# Spring_-_Schematic.net
KiCad netlist of a schematic drawn in EasyEDA
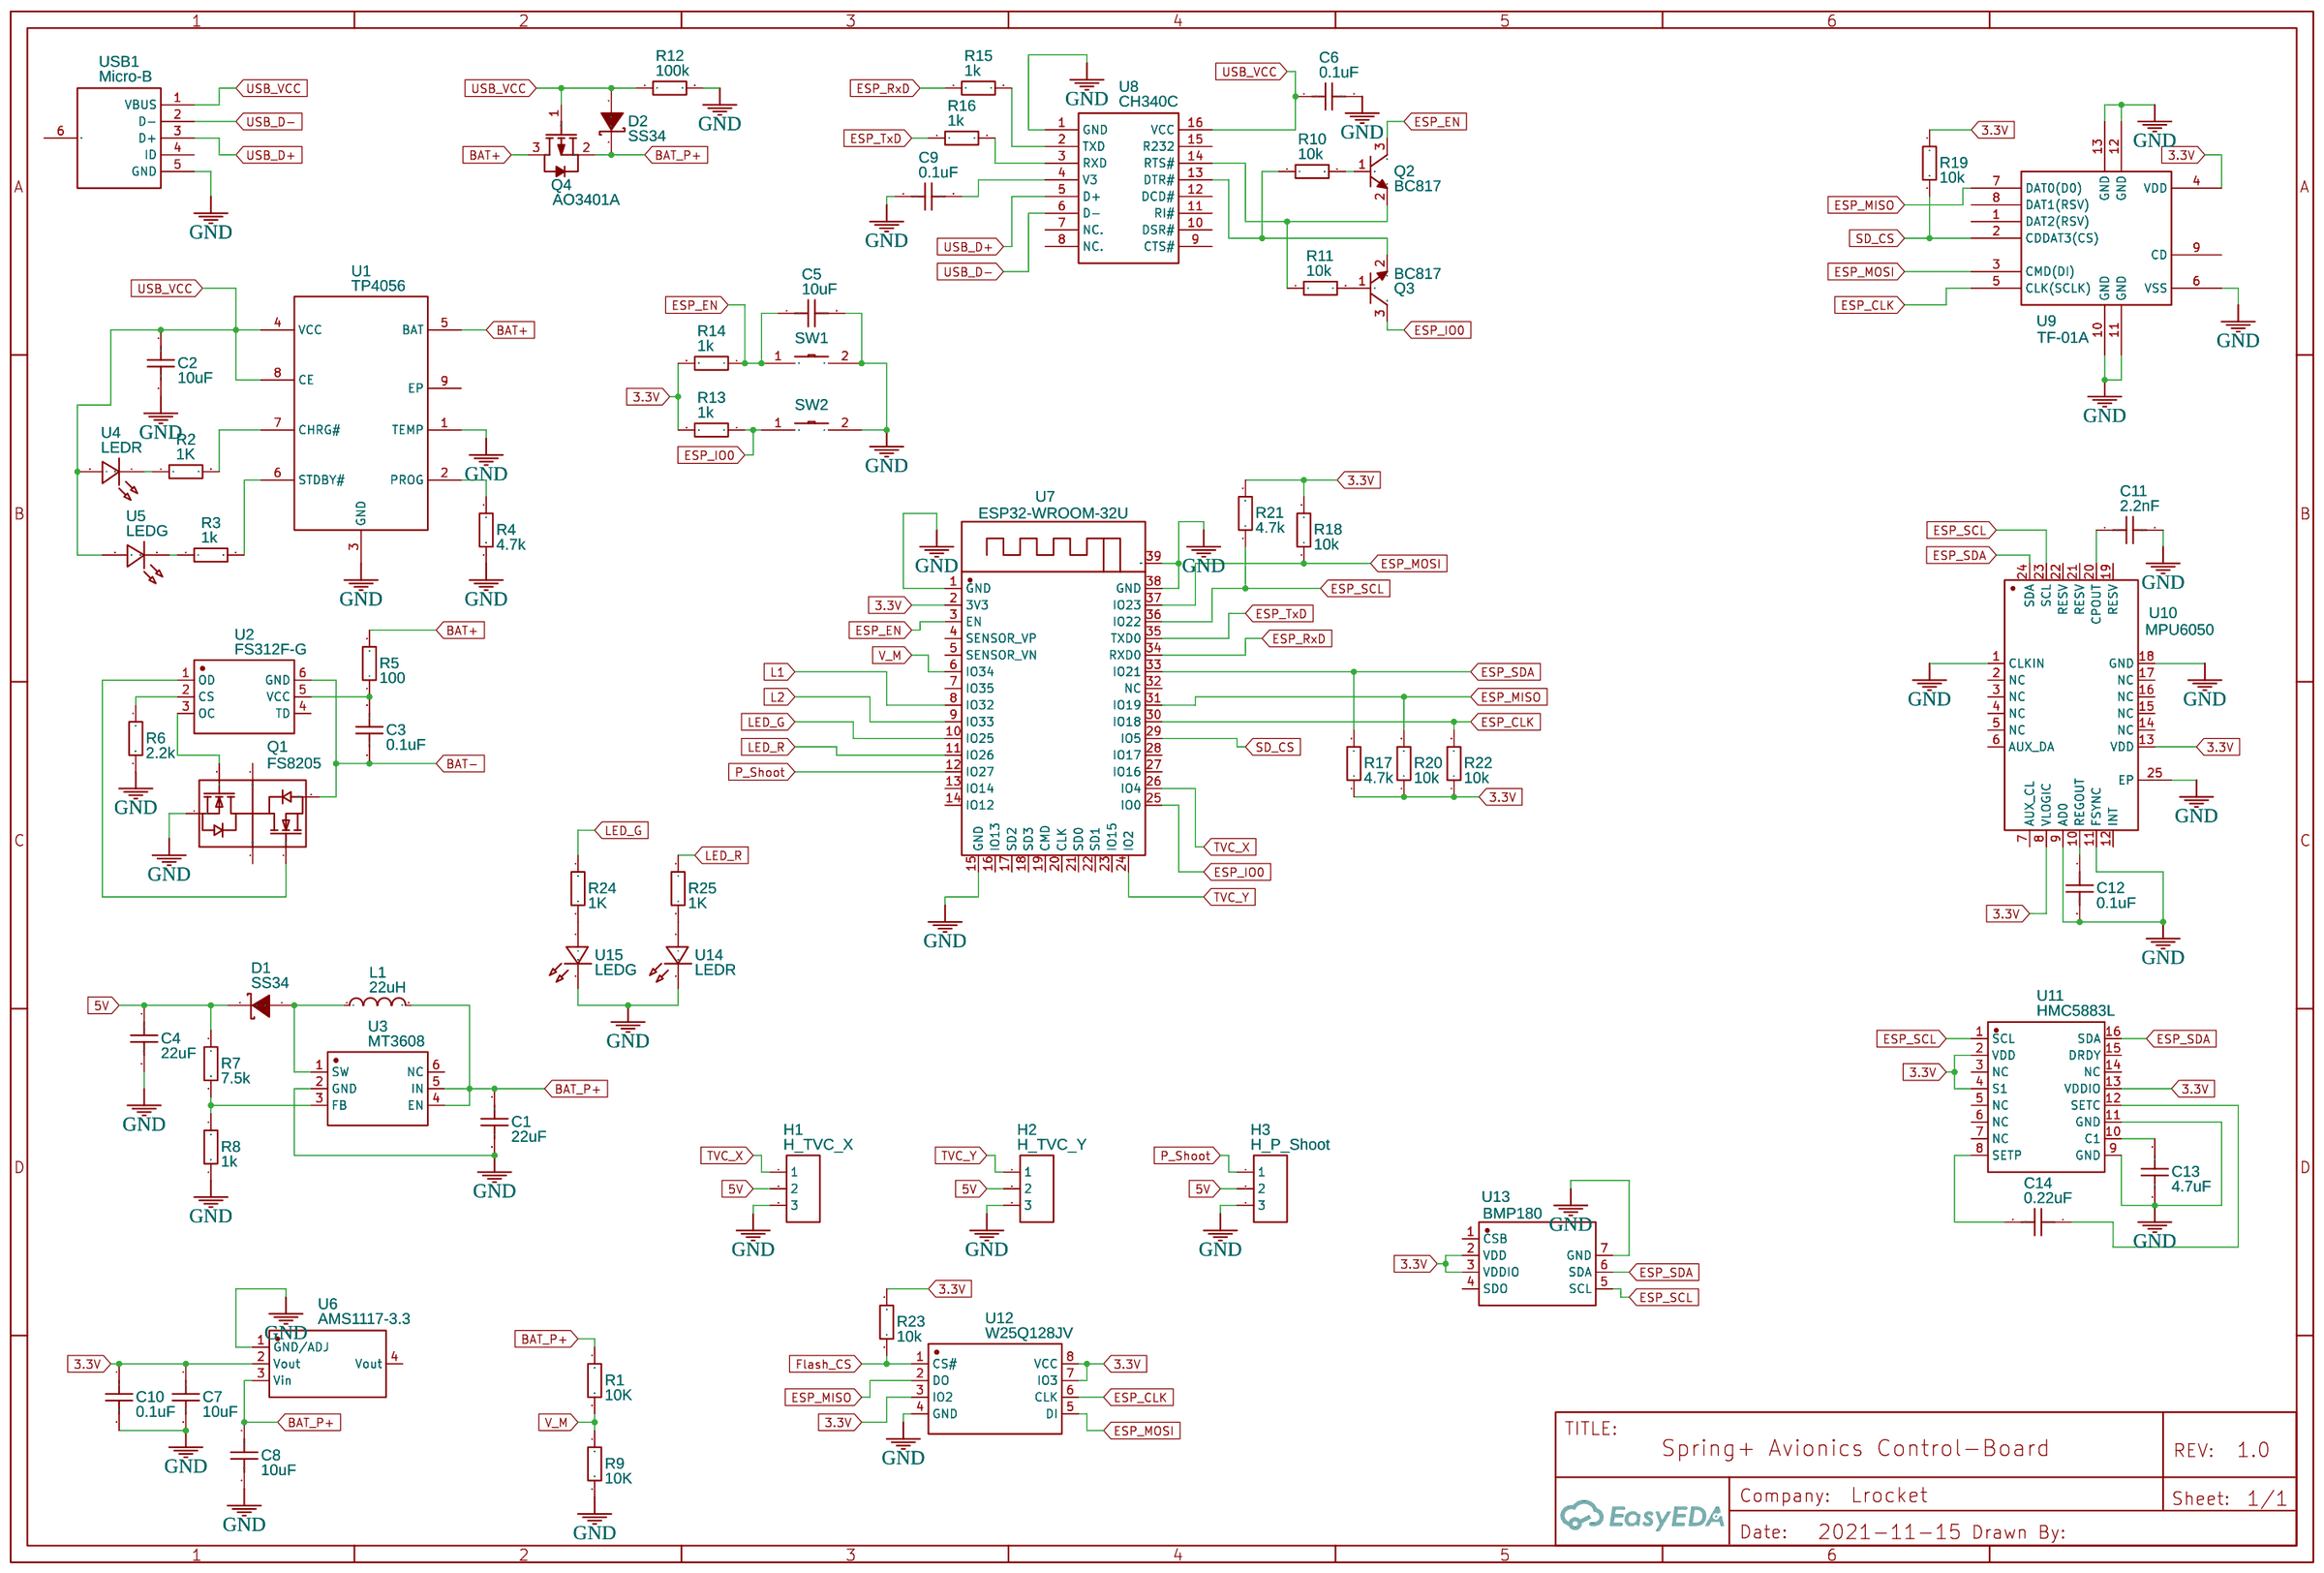
[diagram p0: schematic sheet]

(export (version "E")
  (design (tool "Eeschema 10.0.6"))
  (components
    (comp (ref "C1")
      (value "22uF")
      (fields
        (field (name "BOM_Manufacturer Part") "C1206X5R106K500NT")
        (field (name "BOM_Supplier Part") "C466808")
      )
      (libsource (lib "") (part "C1206X5R106K500NT"))
    )
    (comp (ref "C2")
      (value "10uF")
      (fields
        (field (name "BOM_Manufacturer Part") "C1206X5R106K500NT")
        (field (name "BOM_Supplier Part") "C466808")
      )
      (libsource (lib "") (part "C1206X5R106K500NT"))
    )
    (comp (ref "C3")
      (value "0.1uF")
      (fields
        (field (name "BOM_Manufacturer Part") "C1206X5R106K500NT")
        (field (name "BOM_Supplier Part") "C466808")
      )
      (libsource (lib "") (part "C1206X5R106K500NT_1"))
    )
    (comp (ref "C4")
      (value "22uF")
      (fields
        (field (name "BOM_Manufacturer Part") "C1206X5R106K500NT")
        (field (name "BOM_Supplier Part") "C466808")
      )
      (libsource (lib "") (part "C1206X5R106K500NT"))
    )
    (comp (ref "C5")
      (value "10uF")
      (fields
        (field (name "BOM_Manufacturer Part") "C1206X5R106K500NT")
        (field (name "BOM_Supplier Part") "C466808")
      )
      (libsource (lib "") (part "C1206X5R106K500NT_2"))
    )
    (comp (ref "C6")
      (value "0.1uF")
      (fields
        (field (name "BOM_Manufacturer Part") "C1206X5R106K500NT")
        (field (name "BOM_Supplier Part") "C466808")
      )
      (libsource (lib "") (part "C1206X5R106K500NT_2"))
    )
    (comp (ref "C7")
      (value "10uF")
      (fields
        (field (name "BOM_Manufacturer Part") "C1206X5R106K500NT")
        (field (name "BOM_Supplier Part") "C466808")
      )
      (libsource (lib "") (part "C1206X5R106K500NT"))
    )
    (comp (ref "C8")
      (value "10uF")
      (fields
        (field (name "BOM_Manufacturer Part") "C1206X5R106K500NT")
        (field (name "BOM_Supplier Part") "C466808")
      )
      (libsource (lib "") (part "C1206X5R106K500NT"))
    )
    (comp (ref "C9")
      (value "0.1uF")
      (fields
        (field (name "BOM_Manufacturer Part") "C1206X5R106K500NT")
        (field (name "BOM_Supplier Part") "C466808")
      )
      (libsource (lib "") (part "C1206X5R106K500NT_2"))
    )
    (comp (ref "C10")
      (value "0.1uF")
      (fields
        (field (name "BOM_Manufacturer Part") "C1206X5R106K500NT")
        (field (name "BOM_Supplier Part") "C466808")
      )
      (libsource (lib "") (part "C1206X5R106K500NT"))
    )
    (comp (ref "C11")
      (value "2.2nF")
      (fields
        (field (name "BOM_Manufacturer Part") "C1206X5R106K500NT")
        (field (name "BOM_Supplier Part") "C466808")
      )
      (libsource (lib "") (part "C1206X5R106K500NT_2"))
    )
    (comp (ref "C12")
      (value "0.1uF")
      (fields
        (field (name "BOM_Manufacturer Part") "C1206X5R106K500NT")
        (field (name "BOM_Supplier Part") "C466808")
      )
      (libsource (lib "") (part "C1206X5R106K500NT"))
    )
    (comp (ref "C13")
      (value "4.7uF")
      (fields
        (field (name "BOM_Manufacturer Part") "C1206X5R106K500NT")
        (field (name "BOM_Supplier Part") "C466808")
      )
      (libsource (lib "") (part "C1206X5R106K500NT_1"))
    )
    (comp (ref "C14")
      (value "0.22uF")
      (fields
        (field (name "BOM_Manufacturer Part") "C1206X5R106K500NT")
        (field (name "BOM_Supplier Part") "C466808")
      )
      (libsource (lib "") (part "C1206X5R106K500NT_3"))
    )
    (comp (ref "D1")
      (value "SS34")
      (fields (field (name "BOM_Supplier Part") "C13763"))
      (libsource (lib "") (part "SS34"))
    )
    (comp (ref "D2")
      (value "SS34")
      (fields (field (name "BOM_Supplier Part") "C13763"))
      (libsource (lib "") (part "SS34_1"))
    )
    (comp (ref "H1")
      (value "H_TVC_X")
      (fields
        (field (name "BOM_Manufacturer Part") "Header2.54mm 1*3P")
        (field (name "BOM_Supplier Part") "C49257")
      )
      (libsource (lib "") (part "Header-Male-2.54_1x3"))
    )
    (comp (ref "H2")
      (value "H_TVC_Y")
      (fields
        (field (name "BOM_Manufacturer Part") "Header2.54mm 1*3P")
        (field (name "BOM_Supplier Part") "C49257")
      )
      (libsource (lib "") (part "Header-Male-2.54_1x3"))
    )
    (comp (ref "H3")
      (value "H_P_Shoot")
      (fields
        (field (name "BOM_Manufacturer Part") "Header2.54mm 1*3P")
        (field (name "BOM_Supplier Part") "C49257")
      )
      (libsource (lib "") (part "Header-Male-2.54_1x3"))
    )
    (comp (ref "L1")
      (value "22uH")
      (fields
        (field (name "BOM_Manufacturer Part") "FXL0630-220-M")
        (field (name "BOM_Supplier Part") "C177244")
      )
      (libsource (lib "") (part "FXL0630-220-M"))
    )
    (comp (ref "Q1")
      (value "FS8205")
      (fields (field (name "BOM_Supplier Part") "C32254"))
      (libsource (lib "") (part "FS8205"))
    )
    (comp (ref "Q2")
      (value "BC817")
      (fields (field (name "BOM_Manufacturer Part") "BC817-25") (field (name "BOM_Supplier Part") "C8588"))
      (libsource (lib "") (part "BC817-25_1"))
    )
    (comp (ref "Q3")
      (value "BC817")
      (fields (field (name "BOM_Manufacturer Part") "BC817-25") (field (name "BOM_Supplier Part") "C8588"))
      (libsource (lib "") (part "BC817-25"))
    )
    (comp (ref "Q4")
      (value "AO3401A")
      (fields (field (name "BOM_Supplier Part") "C15127"))
      (libsource (lib "") (part "AO3401A"))
    )
    (comp (ref "R1")
      (value "10K")
      (fields
        (field (name "BOM_Manufacturer Part") "RMCF1206JT10K0")
        (field (name "BOM_Supplier Part") "C237800")
      )
      (libsource (lib "") (part "RMCF1206JT10K0"))
    )
    (comp (ref "R2")
      (value "1K")
      (fields
        (field (name "BOM_Manufacturer Part") "RMCF1206JT10K0")
        (field (name "BOM_Supplier Part") "C237800")
      )
      (libsource (lib "") (part "RMCF1206JT10K0_1"))
    )
    (comp (ref "R3")
      (value "1k")
      (fields
        (field (name "BOM_Manufacturer Part") "RMCF1206JT10K0")
        (field (name "BOM_Supplier Part") "C237800")
      )
      (libsource (lib "") (part "RMCF1206JT10K0_1"))
    )
    (comp (ref "R4")
      (value "4.7k")
      (fields
        (field (name "BOM_Manufacturer Part") "RMCF1206JT10K0")
        (field (name "BOM_Supplier Part") "C237800")
      )
      (libsource (lib "") (part "RMCF1206JT10K0"))
    )
    (comp (ref "R5")
      (value "100")
      (fields
        (field (name "BOM_Manufacturer Part") "RMCF1206JT10K0")
        (field (name "BOM_Supplier Part") "C237800")
      )
      (libsource (lib "") (part "RMCF1206JT10K0_3"))
    )
    (comp (ref "R6")
      (value "2.2k")
      (fields
        (field (name "BOM_Manufacturer Part") "RMCF1206JT10K0")
        (field (name "BOM_Supplier Part") "C237800")
      )
      (libsource (lib "") (part "RMCF1206JT10K0"))
    )
    (comp (ref "R7")
      (value "7.5k")
      (fields
        (field (name "BOM_Manufacturer Part") "RMCF1206JT10K0")
        (field (name "BOM_Supplier Part") "C237800")
      )
      (libsource (lib "") (part "RMCF1206JT10K0"))
    )
    (comp (ref "R8")
      (value "1k")
      (fields
        (field (name "BOM_Manufacturer Part") "RMCF1206JT10K0")
        (field (name "BOM_Supplier Part") "C237800")
      )
      (libsource (lib "") (part "RMCF1206JT10K0"))
    )
    (comp (ref "R9")
      (value "10K")
      (fields
        (field (name "BOM_Manufacturer Part") "RMCF1206JT10K0")
        (field (name "BOM_Supplier Part") "C237800")
      )
      (libsource (lib "") (part "RMCF1206JT10K0"))
    )
    (comp (ref "R10")
      (value "10k")
      (fields
        (field (name "BOM_Manufacturer Part") "RMCF1206JT10K0")
        (field (name "BOM_Supplier Part") "C237800")
      )
      (libsource (lib "") (part "RMCF1206JT10K0_1"))
    )
    (comp (ref "R11")
      (value "10k")
      (fields
        (field (name "BOM_Manufacturer Part") "RMCF1206JT10K0")
        (field (name "BOM_Supplier Part") "C237800")
      )
      (libsource (lib "") (part "RMCF1206JT10K0_1"))
    )
    (comp (ref "R12")
      (value "100k")
      (fields
        (field (name "BOM_Manufacturer Part") "RMCF1206JT10K0")
        (field (name "BOM_Supplier Part") "C237800")
      )
      (libsource (lib "") (part "RMCF1206JT10K0_1"))
    )
    (comp (ref "R13")
      (value "1k")
      (fields
        (field (name "BOM_Manufacturer Part") "RMCF1206JT10K0")
        (field (name "BOM_Supplier Part") "C237800")
      )
      (libsource (lib "") (part "RMCF1206JT10K0_2"))
    )
    (comp (ref "R14")
      (value "1k")
      (fields
        (field (name "BOM_Manufacturer Part") "RMCF1206JT10K0")
        (field (name "BOM_Supplier Part") "C237800")
      )
      (libsource (lib "") (part "RMCF1206JT10K0_2"))
    )
    (comp (ref "R15")
      (value "1k")
      (fields
        (field (name "BOM_Manufacturer Part") "RMCF1206JT10K0")
        (field (name "BOM_Supplier Part") "C237800")
      )
      (libsource (lib "") (part "RMCF1206JT10K0_1"))
    )
    (comp (ref "R16")
      (value "1k")
      (fields
        (field (name "BOM_Manufacturer Part") "RMCF1206JT10K0")
        (field (name "BOM_Supplier Part") "C237800")
      )
      (libsource (lib "") (part "RMCF1206JT10K0_1"))
    )
    (comp (ref "R17")
      (value "4.7k")
      (fields
        (field (name "BOM_Manufacturer Part") "RMCF1206JT10K0")
        (field (name "BOM_Supplier Part") "C237800")
      )
      (libsource (lib "") (part "RMCF1206JT10K0_3"))
    )
    (comp (ref "R18")
      (value "10k")
      (fields
        (field (name "BOM_Manufacturer Part") "RMCF1206JT10K0")
        (field (name "BOM_Supplier Part") "C237800")
      )
      (libsource (lib "") (part "RMCF1206JT10K0_3"))
    )
    (comp (ref "R19")
      (value "10k")
      (fields
        (field (name "BOM_Manufacturer Part") "RMCF1206JT10K0")
        (field (name "BOM_Supplier Part") "C237800")
      )
      (libsource (lib "") (part "RMCF1206JT10K0"))
    )
    (comp (ref "R20")
      (value "10k")
      (fields
        (field (name "BOM_Manufacturer Part") "RMCF1206JT10K0")
        (field (name "BOM_Supplier Part") "C237800")
      )
      (libsource (lib "") (part "RMCF1206JT10K0_3"))
    )
    (comp (ref "R21")
      (value "4.7k")
      (fields
        (field (name "BOM_Manufacturer Part") "RMCF1206JT10K0")
        (field (name "BOM_Supplier Part") "C237800")
      )
      (libsource (lib "") (part "RMCF1206JT10K0_3"))
    )
    (comp (ref "R22")
      (value "10k")
      (fields
        (field (name "BOM_Manufacturer Part") "RMCF1206JT10K0")
        (field (name "BOM_Supplier Part") "C237800")
      )
      (libsource (lib "") (part "RMCF1206JT10K0_3"))
    )
    (comp (ref "R23")
      (value "10k")
      (fields
        (field (name "BOM_Manufacturer Part") "RMCF1206JT10K0")
        (field (name "BOM_Supplier Part") "C237800")
      )
      (libsource (lib "") (part "RMCF1206JT10K0_3"))
    )
    (comp (ref "R24")
      (value "1K")
      (fields
        (field (name "BOM_Manufacturer Part") "RMCF1206JT10K0")
        (field (name "BOM_Supplier Part") "C237800")
      )
      (libsource (lib "") (part "RMCF1206JT10K0"))
    )
    (comp (ref "R25")
      (value "1K")
      (fields
        (field (name "BOM_Manufacturer Part") "RMCF1206JT10K0")
        (field (name "BOM_Supplier Part") "C237800")
      )
      (libsource (lib "") (part "RMCF1206JT10K0"))
    )
    (comp (ref "SW1")
      (value "TS-1101-C-W")
      (fields (field (name "BOM_Supplier Part") "C318938"))
      (libsource (lib "") (part "TS-1101-C-W"))
    )
    (comp (ref "SW2")
      (value "TS-1101-C-W")
      (fields (field (name "BOM_Supplier Part") "C318938"))
      (libsource (lib "") (part "TS-1101-C-W"))
    )
    (comp (ref "U1")
      (value "TP4056")
      (fields (field (name "BOM_Supplier Part") "C16581"))
      (libsource (lib "") (part "TP4056"))
    )
    (comp (ref "U2")
      (value "FS312F-G")
      (fields (field (name "BOM_Supplier Part") "C82736"))
      (libsource (lib "") (part "FS312F-G"))
    )
    (comp (ref "U3")
      (value "MT3608")
      (fields (field (name "BOM_Supplier Part") "C84817"))
      (libsource (lib "") (part "MT3608"))
    )
    (comp (ref "U4")
      (value "LEDR")
      (fields (field (name "BOM_Manufacturer Part") "SFH 2701") (field (name "BOM_Supplier Part") "C66361"))
      (libsource (lib "") (part "SFH 2701_1"))
    )
    (comp (ref "U5")
      (value "LEDG")
      (fields (field (name "BOM_Manufacturer Part") "SFH 2701") (field (name "BOM_Supplier Part") "C66361"))
      (libsource (lib "") (part "SFH 2701_1"))
    )
    (comp (ref "U6")
      (value "AMS1117-3.3")
      (fields (field (name "BOM_Supplier Part") "C6186"))
      (libsource (lib "") (part "AMS1117-3.3"))
    )
    (comp (ref "U7")
      (value "ESP32-WROOM-32U")
      (fields (field (name "BOM_Supplier Part") "C328062"))
      (libsource (lib "") (part "ESP32-WROOM-32U"))
    )
    (comp (ref "U8")
      (value "CH340C")
      (fields (field (name "BOM_Supplier Part") "C84681"))
      (libsource (lib "") (part "CH340C"))
    )
    (comp (ref "U9")
      (value "TF-01A")
      (fields (field (name "BOM_Supplier Part") "C91145"))
      (libsource (lib "") (part "TF-01A"))
    )
    (comp (ref "U10")
      (value "MPU6050")
      (fields
        (field (name "BOM_Manufacturer Part") "MPU6050-YJLTY")
        (field (name "BOM_Supplier Part") "C2912107")
      )
      (libsource (lib "") (part "MPU6050-YJLTY"))
    )
    (comp (ref "U11")
      (value "HMC5883L")
      (fields (field (name "BOM_Supplier Part") "C2859540"))
      (libsource (lib "") (part "HMC5883L"))
    )
    (comp (ref "U12")
      (value "W25Q128JV")
      (fields
        (field (name "BOM_Manufacturer Part") "W25Q128JVSIQTR")
        (field (name "BOM_Supplier Part") "C97521")
      )
      (libsource (lib "") (part "W25Q128JVSIQTR"))
    )
    (comp (ref "U13")
      (value "BMP180")
      (fields (field (name "BOM_Supplier Part") "C438474"))
      (libsource (lib "") (part "BMP180"))
    )
    (comp (ref "U14")
      (value "LEDR")
      (fields (field (name "BOM_Manufacturer Part") "SFH 2701") (field (name "BOM_Supplier Part") "C66361"))
      (libsource (lib "") (part "SFH 2701"))
    )
    (comp (ref "U15")
      (value "LEDG")
      (fields (field (name "BOM_Manufacturer Part") "SFH 2701") (field (name "BOM_Supplier Part") "C66361"))
      (libsource (lib "") (part "SFH 2701"))
    )
    (comp (ref "USB1")
      (value "Micro-B")
      (fields
        (field (name "BOM_Manufacturer Part") "U254-051T-4BH83-S1S")
        (field (name "BOM_Supplier Part") "C319160")
      )
      (libsource (lib "") (part "U254-051T-4BH83-S1S"))
    )
  )
  (nets
    (net (code "1") (name "3.3V") (class "Default")
      (node (ref "C10") (pin "1") (pinfunction "1_1") (pintype "unspecified"))
      (node (ref "C7") (pin "1") (pinfunction "1_1") (pintype "unspecified"))
      (node (ref "R13") (pin "2") (pinfunction "2_2") (pintype "unspecified"))
      (node (ref "R14") (pin "2") (pinfunction "2_2") (pintype "unspecified"))
      (node (ref "R17") (pin "1") (pinfunction "1_1") (pintype "unspecified"))
      (node (ref "R18") (pin "2") (pinfunction "2_2") (pintype "unspecified"))
      (node (ref "R19") (pin "1") (pinfunction "1_1") (pintype "unspecified"))
      (node (ref "R20") (pin "1") (pinfunction "1_1") (pintype "unspecified"))
      (node (ref "R21") (pin "2") (pinfunction "2_2") (pintype "unspecified"))
      (node (ref "R22") (pin "1") (pinfunction "1_1") (pintype "unspecified"))
      (node (ref "R23") (pin "2") (pinfunction "2_2") (pintype "unspecified"))
      (node (ref "U10") (pin "13") (pinfunction "VDD_13") (pintype "unspecified"))
      (node (ref "U10") (pin "8") (pinfunction "VLOGIC_8") (pintype "unspecified"))
      (node (ref "U11") (pin "13") (pinfunction "VDDIO_13") (pintype "unspecified"))
      (node (ref "U11") (pin "2") (pinfunction "VDD_2") (pintype "unspecified"))
      (node (ref "U11") (pin "4") (pinfunction "S1_4") (pintype "unspecified"))
      (node (ref "U12") (pin "3") (pinfunction "IO2_3") (pintype "unspecified"))
      (node (ref "U12") (pin "7") (pinfunction "IO3_7") (pintype "unspecified"))
      (node (ref "U12") (pin "8") (pinfunction "VCC_8") (pintype "unspecified"))
      (node (ref "U13") (pin "2") (pinfunction "VDD_2") (pintype "unspecified"))
      (node (ref "U13") (pin "3") (pinfunction "VDDIO_3") (pintype "unspecified"))
      (node (ref "U6") (pin "2") (pinfunction "Vout_2") (pintype "unspecified"))
      (node (ref "U7") (pin "2") (pinfunction "3V3_2") (pintype "unspecified"))
      (node (ref "U9") (pin "4") (pinfunction "VDD_4") (pintype "input"))
    )
    (net (code "2") (name "5V") (class "Default")
      (node (ref "C4") (pin "1") (pinfunction "1_1") (pintype "unspecified"))
      (node (ref "D1") (pin "2") (pinfunction "K_2") (pintype "unspecified"))
      (node (ref "H1") (pin "2") (pinfunction "2_2") (pintype "input"))
      (node (ref "H2") (pin "2") (pinfunction "2_2") (pintype "input"))
      (node (ref "H3") (pin "2") (pinfunction "2_2") (pintype "input"))
      (node (ref "R7") (pin "1") (pinfunction "1_1") (pintype "unspecified"))
    )
    (net (code "3") (name "BAT+") (class "Default")
      (node (ref "Q4") (pin "3") (pinfunction "D_3") (pintype "unspecified"))
      (node (ref "R5") (pin "2") (pinfunction "2_2") (pintype "unspecified"))
      (node (ref "U1") (pin "5") (pinfunction "BAT_5") (pintype "unspecified"))
    )
    (net (code "4") (name "BAT-") (class "Default")
      (node (ref "C3") (pin "1") (pinfunction "1_1") (pintype "unspecified"))
      (node (ref "Q1") (pin "3") (pinfunction "S2_3") (pintype "unspecified"))
      (node (ref "U2") (pin "6") (pinfunction "GND_6") (pintype "unspecified"))
    )
    (net (code "5") (name "BAT_P+") (class "Default")
      (node (ref "C1") (pin "1") (pinfunction "1_1") (pintype "unspecified"))
      (node (ref "C8") (pin "1") (pinfunction "1_1") (pintype "unspecified"))
      (node (ref "D2") (pin "2") (pinfunction "K_2") (pintype "unspecified"))
      (node (ref "L1") (pin "2") (pinfunction "2_2") (pintype "unspecified"))
      (node (ref "Q4") (pin "2") (pinfunction "S_2") (pintype "unspecified"))
      (node (ref "R1") (pin "1") (pinfunction "1_1") (pintype "unspecified"))
      (node (ref "U3") (pin "4") (pinfunction "EN_4") (pintype "unspecified"))
      (node (ref "U3") (pin "5") (pinfunction "IN_5") (pintype "unspecified"))
      (node (ref "U6") (pin "3") (pinfunction "Vin_3") (pintype "unspecified"))
    )
    (net (code "6") (name "ESP_CLK") (class "Default")
      (node (ref "R22") (pin "2") (pinfunction "2_2") (pintype "unspecified"))
      (node (ref "U12") (pin "6") (pinfunction "CLK_6") (pintype "unspecified"))
      (node (ref "U7") (pin "30") (pinfunction "IO18_30") (pintype "unspecified"))
      (node (ref "U9") (pin "5") (pinfunction "CLK(SCLK)_5") (pintype "input"))
    )
    (net (code "7") (name "ESP_EN") (class "Default")
      (node (ref "C5") (pin "1") (pinfunction "1_1") (pintype "unspecified"))
      (node (ref "Q2") (pin "3") (pinfunction "C_3") (pintype "unspecified"))
      (node (ref "R14") (pin "1") (pinfunction "1_1") (pintype "unspecified"))
      (node (ref "SW1") (pin "1") (pinfunction "1_1") (pintype "unspecified"))
      (node (ref "U7") (pin "3") (pinfunction "EN_3") (pintype "unspecified"))
    )
    (net (code "8") (name "ESP_IO0") (class "Default")
      (node (ref "Q3") (pin "3") (pinfunction "C_3") (pintype "unspecified"))
      (node (ref "R13") (pin "1") (pinfunction "1_1") (pintype "unspecified"))
      (node (ref "SW2") (pin "1") (pinfunction "1_1") (pintype "unspecified"))
      (node (ref "U7") (pin "25") (pinfunction "IO0_25") (pintype "unspecified"))
    )
    (net (code "9") (name "ESP_MISO") (class "Default")
      (node (ref "R20") (pin "2") (pinfunction "2_2") (pintype "unspecified"))
      (node (ref "U12") (pin "2") (pinfunction "DO_2") (pintype "unspecified"))
      (node (ref "U7") (pin "31") (pinfunction "IO19_31") (pintype "unspecified"))
      (node (ref "U9") (pin "7") (pinfunction "DAT0(D0)_7") (pintype "bidirectional"))
    )
    (net (code "10") (name "ESP_MOSI") (class "Default")
      (node (ref "R18") (pin "1") (pinfunction "1_1") (pintype "unspecified"))
      (node (ref "U12") (pin "5") (pinfunction "DI_5") (pintype "unspecified"))
      (node (ref "U7") (pin "37") (pinfunction "IO23_37") (pintype "unspecified"))
      (node (ref "U9") (pin "3") (pinfunction "CMD(DI)_3") (pintype "input"))
    )
    (net (code "11") (name "ESP_RxD") (class "Default")
      (node (ref "R15") (pin "1") (pinfunction "1_1") (pintype "unspecified"))
      (node (ref "U7") (pin "34") (pinfunction "RXD0_34") (pintype "unspecified"))
    )
    (net (code "12") (name "ESP_SCL") (class "Default")
      (node (ref "R21") (pin "1") (pinfunction "1_1") (pintype "unspecified"))
      (node (ref "U10") (pin "23") (pinfunction "SCL_23") (pintype "unspecified"))
      (node (ref "U11") (pin "1") (pinfunction "SCL_1") (pintype "unspecified"))
      (node (ref "U13") (pin "5") (pinfunction "SCL_5") (pintype "unspecified"))
      (node (ref "U7") (pin "36") (pinfunction "IO22_36") (pintype "unspecified"))
    )
    (net (code "13") (name "ESP_SDA") (class "Default")
      (node (ref "R17") (pin "2") (pinfunction "2_2") (pintype "unspecified"))
      (node (ref "U10") (pin "24") (pinfunction "SDA_24") (pintype "unspecified"))
      (node (ref "U11") (pin "16") (pinfunction "SDA_16") (pintype "unspecified"))
      (node (ref "U13") (pin "6") (pinfunction "SDA_6") (pintype "unspecified"))
      (node (ref "U7") (pin "33") (pinfunction "IO21_33") (pintype "unspecified"))
    )
    (net (code "14") (name "ESP_TxD") (class "Default")
      (node (ref "R16") (pin "1") (pinfunction "1_1") (pintype "unspecified"))
      (node (ref "U7") (pin "35") (pinfunction "TXD0_35") (pintype "unspecified"))
    )
    (net (code "15") (name "Flash_CS") (class "Default")
      (node (ref "R23") (pin "1") (pinfunction "1_1") (pintype "unspecified"))
      (node (ref "U12") (pin "1") (pinfunction "CS#_1") (pintype "unspecified"))
    )
    (net (code "16") (name "GND") (class "Default")
      (node (ref "C1") (pin "2") (pinfunction "2_2") (pintype "unspecified"))
      (node (ref "C10") (pin "2") (pinfunction "2_2") (pintype "unspecified"))
      (node (ref "C11") (pin "2") (pinfunction "2_2") (pintype "unspecified"))
      (node (ref "C12") (pin "2") (pinfunction "2_2") (pintype "unspecified"))
      (node (ref "C13") (pin "1") (pinfunction "1_1") (pintype "unspecified"))
      (node (ref "C2") (pin "2") (pinfunction "2_2") (pintype "unspecified"))
      (node (ref "C4") (pin "2") (pinfunction "2_2") (pintype "unspecified"))
      (node (ref "C5") (pin "2") (pinfunction "2_2") (pintype "unspecified"))
      (node (ref "C6") (pin "2") (pinfunction "2_2") (pintype "unspecified"))
      (node (ref "C7") (pin "2") (pinfunction "2_2") (pintype "unspecified"))
      (node (ref "C8") (pin "2") (pinfunction "2_2") (pintype "unspecified"))
      (node (ref "C9") (pin "1") (pinfunction "1_1") (pintype "unspecified"))
      (node (ref "H1") (pin "3") (pinfunction "3_3") (pintype "input"))
      (node (ref "H2") (pin "3") (pinfunction "3_3") (pintype "input"))
      (node (ref "H3") (pin "3") (pinfunction "3_3") (pintype "input"))
      (node (ref "Q1") (pin "1") (pinfunction "S1_1") (pintype "unspecified"))
      (node (ref "R12") (pin "2") (pinfunction "2_2") (pintype "unspecified"))
      (node (ref "R4") (pin "2") (pinfunction "2_2") (pintype "unspecified"))
      (node (ref "R6") (pin "2") (pinfunction "2_2") (pintype "unspecified"))
      (node (ref "R8") (pin "2") (pinfunction "2_2") (pintype "unspecified"))
      (node (ref "R9") (pin "2") (pinfunction "2_2") (pintype "unspecified"))
      (node (ref "SW1") (pin "2") (pinfunction "2_2") (pintype "unspecified"))
      (node (ref "SW2") (pin "2") (pinfunction "2_2") (pintype "unspecified"))
      (node (ref "U1") (pin "1") (pinfunction "TEMP_1") (pintype "unspecified"))
      (node (ref "U1") (pin "3") (pinfunction "GND_3") (pintype "unspecified"))
      (node (ref "U10") (pin "1") (pinfunction "CLKIN_1") (pintype "unspecified"))
      (node (ref "U10") (pin "11") (pinfunction "FSYNC_11") (pintype "unspecified"))
      (node (ref "U10") (pin "18") (pinfunction "GND_18") (pintype "unspecified"))
      (node (ref "U10") (pin "25") (pinfunction "EP_25") (pintype "unspecified"))
      (node (ref "U10") (pin "9") (pinfunction "AD0_9") (pintype "unspecified"))
      (node (ref "U11") (pin "11") (pinfunction "GND_11") (pintype "unspecified"))
      (node (ref "U11") (pin "9") (pinfunction "GND_9") (pintype "unspecified"))
      (node (ref "U12") (pin "4") (pinfunction "GND_4") (pintype "unspecified"))
      (node (ref "U13") (pin "7") (pinfunction "GND_7") (pintype "unspecified"))
      (node (ref "U14") (pin "1") (pinfunction "C_1") (pintype "unspecified"))
      (node (ref "U15") (pin "1") (pinfunction "C_1") (pintype "unspecified"))
      (node (ref "U3") (pin "2") (pinfunction "GND_2") (pintype "unspecified"))
      (node (ref "U6") (pin "1") (pinfunction "GND/ADJ_1") (pintype "unspecified"))
      (node (ref "U7") (pin "1") (pinfunction "GND_1") (pintype "unspecified"))
      (node (ref "U7") (pin "15") (pinfunction "GND_15") (pintype "unspecified"))
      (node (ref "U7") (pin "38") (pinfunction "GND_38") (pintype "unspecified"))
      (node (ref "U7") (pin "39") (pinfunction "GND_39") (pintype "unspecified"))
      (node (ref "U8") (pin "1") (pinfunction "GND_1") (pintype "unspecified"))
      (node (ref "U9") (pin "10") (pinfunction "GND_10") (pintype "input"))
      (node (ref "U9") (pin "11") (pinfunction "GND_11") (pintype "input"))
      (node (ref "U9") (pin "12") (pinfunction "GND_12") (pintype "input"))
      (node (ref "U9") (pin "13") (pinfunction "GND_13") (pintype "input"))
      (node (ref "U9") (pin "6") (pinfunction "VSS_6") (pintype "input"))
      (node (ref "USB1") (pin "5") (pinfunction "GND_5") (pintype "input"))
    )
    (net (code "17") (name "L1") (class "Default")
      (node (ref "U7") (pin "8") (pinfunction "IO32_8") (pintype "unspecified"))
    )
    (net (code "18") (name "L2") (class "Default")
      (node (ref "U7") (pin "9") (pinfunction "IO33_9") (pintype "unspecified"))
    )
    (net (code "19") (name "LED_G") (class "Default")
      (node (ref "R24") (pin "1") (pinfunction "1_1") (pintype "unspecified"))
      (node (ref "U7") (pin "10") (pinfunction "IO25_10") (pintype "unspecified"))
    )
    (net (code "20") (name "LED_R") (class "Default")
      (node (ref "R25") (pin "1") (pinfunction "1_1") (pintype "unspecified"))
      (node (ref "U7") (pin "11") (pinfunction "IO26_11") (pintype "unspecified"))
    )
    (net (code "21") (name "Net-(D1-A)") (class "Default")
      (node (ref "D1") (pin "1") (pinfunction "A_1") (pintype "unspecified"))
      (node (ref "L1") (pin "1") (pinfunction "1_1") (pintype "unspecified"))
      (node (ref "U3") (pin "1") (pinfunction "SW_1") (pintype "unspecified"))
    )
    (net (code "22") (name "Net-(Q1-G1)") (class "Default")
      (node (ref "Q1") (pin "6") (pinfunction "G1_6") (pintype "unspecified"))
      (node (ref "U2") (pin "3") (pinfunction "OC_3") (pintype "unspecified"))
    )
    (net (code "23") (name "Net-(Q1-G2)") (class "Default")
      (node (ref "Q1") (pin "4") (pinfunction "G2_4") (pintype "unspecified"))
      (node (ref "U2") (pin "1") (pinfunction "OD_1") (pintype "unspecified"))
    )
    (net (code "24") (name "Net-(Q2-B)") (class "Default")
      (node (ref "Q2") (pin "1") (pinfunction "B_1") (pintype "unspecified"))
      (node (ref "R10") (pin "2") (pinfunction "2_2") (pintype "unspecified"))
    )
    (net (code "25") (name "Net-(Q2-E)") (class "Default")
      (node (ref "Q2") (pin "2") (pinfunction "E_2") (pintype "unspecified"))
      (node (ref "R11") (pin "1") (pinfunction "1_1") (pintype "unspecified"))
      (node (ref "U8") (pin "14") (pinfunction "RTS#_14") (pintype "unspecified"))
    )
    (net (code "26") (name "Net-(Q3-B)") (class "Default")
      (node (ref "Q3") (pin "1") (pinfunction "B_1") (pintype "unspecified"))
      (node (ref "R11") (pin "2") (pinfunction "2_2") (pintype "unspecified"))
    )
    (net (code "27") (name "Net-(Q3-E)") (class "Default")
      (node (ref "Q3") (pin "2") (pinfunction "E_2") (pintype "unspecified"))
      (node (ref "R10") (pin "1") (pinfunction "1_1") (pintype "unspecified"))
      (node (ref "U8") (pin "13") (pinfunction "DTR#_13") (pintype "unspecified"))
    )
    (net (code "28") (name "Net-(U1-CHRG#)") (class "Default")
      (node (ref "R2") (pin "2") (pinfunction "2_2") (pintype "unspecified"))
      (node (ref "U1") (pin "7") (pinfunction "CHRG#_7") (pintype "unspecified"))
    )
    (net (code "29") (name "Net-(U1-PROG)") (class "Default")
      (node (ref "R4") (pin "1") (pinfunction "1_1") (pintype "unspecified"))
      (node (ref "U1") (pin "2") (pinfunction "PROG_2") (pintype "unspecified"))
    )
    (net (code "30") (name "Net-(U1-STDBY#)") (class "Default")
      (node (ref "R3") (pin "2") (pinfunction "2_2") (pintype "unspecified"))
      (node (ref "U1") (pin "6") (pinfunction "STDBY#_6") (pintype "unspecified"))
    )
    (net (code "31") (name "Net-(U2-CS)") (class "Default")
      (node (ref "R6") (pin "1") (pinfunction "1_1") (pintype "unspecified"))
      (node (ref "U2") (pin "2") (pinfunction "CS_2") (pintype "unspecified"))
    )
    (net (code "32") (name "Net-(U2-VCC)") (class "Default")
      (node (ref "C3") (pin "2") (pinfunction "2_2") (pintype "unspecified"))
      (node (ref "R5") (pin "1") (pinfunction "1_1") (pintype "unspecified"))
      (node (ref "U2") (pin "5") (pinfunction "VCC_5") (pintype "unspecified"))
    )
    (net (code "33") (name "Net-(U3-FB)") (class "Default")
      (node (ref "R7") (pin "2") (pinfunction "2_2") (pintype "unspecified"))
      (node (ref "R8") (pin "1") (pinfunction "1_1") (pintype "unspecified"))
      (node (ref "U3") (pin "3") (pinfunction "FB_3") (pintype "unspecified"))
    )
    (net (code "34") (name "Net-(U4-C)") (class "Default")
      (node (ref "R2") (pin "1") (pinfunction "1_1") (pintype "unspecified"))
      (node (ref "U4") (pin "1") (pinfunction "C_1") (pintype "unspecified"))
    )
    (net (code "35") (name "Net-(U5-C)") (class "Default")
      (node (ref "R3") (pin "1") (pinfunction "1_1") (pintype "unspecified"))
      (node (ref "U5") (pin "1") (pinfunction "C_1") (pintype "unspecified"))
    )
    (net (code "36") (name "Net-(U8-RXD)") (class "Default")
      (node (ref "R16") (pin "2") (pinfunction "2_2") (pintype "unspecified"))
      (node (ref "U8") (pin "3") (pinfunction "RXD_3") (pintype "unspecified"))
    )
    (net (code "37") (name "Net-(U8-TXD)") (class "Default")
      (node (ref "R15") (pin "2") (pinfunction "2_2") (pintype "unspecified"))
      (node (ref "U8") (pin "2") (pinfunction "TXD_2") (pintype "unspecified"))
    )
    (net (code "38") (name "Net-(U8-V3)") (class "Default")
      (node (ref "C9") (pin "2") (pinfunction "2_2") (pintype "unspecified"))
      (node (ref "U8") (pin "4") (pinfunction "V3_4") (pintype "unspecified"))
    )
    (net (code "39") (name "Net-(U10-CPOUT)") (class "Default")
      (node (ref "C11") (pin "1") (pinfunction "1_1") (pintype "unspecified"))
      (node (ref "U10") (pin "20") (pinfunction "CPOUT_20") (pintype "unspecified"))
    )
    (net (code "40") (name "Net-(U10-REGOUT)") (class "Default")
      (node (ref "C12") (pin "1") (pinfunction "1_1") (pintype "unspecified"))
      (node (ref "U10") (pin "10") (pinfunction "REGOUT_10") (pintype "unspecified"))
    )
    (net (code "41") (name "Net-(U11-C1)") (class "Default")
      (node (ref "C13") (pin "2") (pinfunction "2_2") (pintype "unspecified"))
      (node (ref "U11") (pin "10") (pinfunction "C1_10") (pintype "unspecified"))
    )
    (net (code "42") (name "Net-(U11-SETC)") (class "Default")
      (node (ref "C14") (pin "1") (pinfunction "1_1") (pintype "unspecified"))
      (node (ref "U11") (pin "12") (pinfunction "SETC_12") (pintype "unspecified"))
    )
    (net (code "43") (name "Net-(U11-SETP)") (class "Default")
      (node (ref "C14") (pin "2") (pinfunction "2_2") (pintype "unspecified"))
      (node (ref "U11") (pin "8") (pinfunction "SETP_8") (pintype "unspecified"))
    )
    (net (code "44") (name "Net-(U14-A)") (class "Default")
      (node (ref "R25") (pin "2") (pinfunction "2_2") (pintype "unspecified"))
      (node (ref "U14") (pin "2") (pinfunction "A_2") (pintype "unspecified"))
    )
    (net (code "45") (name "Net-(U15-A)") (class "Default")
      (node (ref "R24") (pin "2") (pinfunction "2_2") (pintype "unspecified"))
      (node (ref "U15") (pin "2") (pinfunction "A_2") (pintype "unspecified"))
    )
    (net (code "46") (name "P_Shoot") (class "Default")
      (node (ref "H3") (pin "1") (pinfunction "1_1") (pintype "input"))
      (node (ref "U7") (pin "12") (pinfunction "IO27_12") (pintype "unspecified"))
    )
    (net (code "47") (name "SD_CS") (class "Default")
      (node (ref "R19") (pin "2") (pinfunction "2_2") (pintype "unspecified"))
      (node (ref "U7") (pin "29") (pinfunction "IO5_29") (pintype "unspecified"))
      (node (ref "U9") (pin "2") (pinfunction "CDDAT3(CS)_2") (pintype "bidirectional"))
    )
    (net (code "48") (name "TVC_X") (class "Default")
      (node (ref "H1") (pin "1") (pinfunction "1_1") (pintype "input"))
      (node (ref "U7") (pin "26") (pinfunction "IO4_26") (pintype "unspecified"))
    )
    (net (code "49") (name "TVC_Y") (class "Default")
      (node (ref "H2") (pin "1") (pinfunction "1_1") (pintype "input"))
      (node (ref "U7") (pin "24") (pinfunction "IO2_24") (pintype "unspecified"))
    )
    (net (code "50") (name "USB_D+") (class "Default")
      (node (ref "U8") (pin "5") (pinfunction "D+_5") (pintype "unspecified"))
      (node (ref "USB1") (pin "3") (pinfunction "D+_3") (pintype "input"))
    )
    (net (code "51") (name "USB_D-") (class "Default")
      (node (ref "U8") (pin "6") (pinfunction "D-_6") (pintype "unspecified"))
      (node (ref "USB1") (pin "2") (pinfunction "D-_2") (pintype "input"))
    )
    (net (code "52") (name "USB_VCC") (class "Default")
      (node (ref "C2") (pin "1") (pinfunction "1_1") (pintype "unspecified"))
      (node (ref "C6") (pin "1") (pinfunction "1_1") (pintype "unspecified"))
      (node (ref "D2") (pin "1") (pinfunction "A_1") (pintype "unspecified"))
      (node (ref "Q4") (pin "1") (pinfunction "G_1") (pintype "unspecified"))
      (node (ref "R12") (pin "1") (pinfunction "1_1") (pintype "unspecified"))
      (node (ref "U1") (pin "4") (pinfunction "VCC_4") (pintype "unspecified"))
      (node (ref "U1") (pin "8") (pinfunction "CE_8") (pintype "unspecified"))
      (node (ref "U4") (pin "2") (pinfunction "A_2") (pintype "unspecified"))
      (node (ref "U5") (pin "2") (pinfunction "A_2") (pintype "unspecified"))
      (node (ref "U8") (pin "16") (pinfunction "VCC_16") (pintype "unspecified"))
      (node (ref "USB1") (pin "1") (pinfunction "VBUS_1") (pintype "input"))
    )
    (net (code "53") (name "V_M") (class "Default")
      (node (ref "R1") (pin "2") (pinfunction "2_2") (pintype "unspecified"))
      (node (ref "R9") (pin "1") (pinfunction "1_1") (pintype "unspecified"))
      (node (ref "U7") (pin "6") (pinfunction "IO34_6") (pintype "unspecified"))
    )
    (net (code "54") (name "unconnected-(Q1-D12-Pad2)") (class "Default")
      (node (ref "Q1") (pin "2") (pinfunction "D12_2") (pintype "unspecified"))
    )
    (net (code "55") (name "unconnected-(Q1-D12-Pad5)") (class "Default")
      (node (ref "Q1") (pin "5") (pinfunction "D12_5") (pintype "unspecified"))
    )
    (net (code "56") (name "unconnected-(U1-EP-Pad9)") (class "Default")
      (node (ref "U1") (pin "9") (pinfunction "EP_9") (pintype "unspecified"))
    )
    (net (code "57") (name "unconnected-(U2-TD-Pad4)") (class "Default")
      (node (ref "U2") (pin "4") (pinfunction "TD_4") (pintype "unspecified"))
    )
    (net (code "58") (name "unconnected-(U3-NC-Pad6)") (class "Default")
      (node (ref "U3") (pin "6") (pinfunction "NC_6") (pintype "unspecified"))
    )
    (net (code "59") (name "unconnected-(U6-Vout-Pad4)") (class "Default")
      (node (ref "U6") (pin "4") (pinfunction "Vout_4") (pintype "unspecified"))
    )
    (net (code "60") (name "unconnected-(U7-CLK-Pad20)") (class "Default")
      (node (ref "U7") (pin "20") (pinfunction "CLK_20") (pintype "unspecified"))
    )
    (net (code "61") (name "unconnected-(U7-CMD-Pad19)") (class "Default")
      (node (ref "U7") (pin "19") (pinfunction "CMD_19") (pintype "unspecified"))
    )
    (net (code "62") (name "unconnected-(U7-IO12-Pad14)") (class "Default")
      (node (ref "U7") (pin "14") (pinfunction "IO12_14") (pintype "unspecified"))
    )
    (net (code "63") (name "unconnected-(U7-IO13-Pad16)") (class "Default")
      (node (ref "U7") (pin "16") (pinfunction "IO13_16") (pintype "unspecified"))
    )
    (net (code "64") (name "unconnected-(U7-IO14-Pad13)") (class "Default")
      (node (ref "U7") (pin "13") (pinfunction "IO14_13") (pintype "unspecified"))
    )
    (net (code "65") (name "unconnected-(U7-IO15-Pad23)") (class "Default")
      (node (ref "U7") (pin "23") (pinfunction "IO15_23") (pintype "unspecified"))
    )
    (net (code "66") (name "unconnected-(U7-IO16-Pad27)") (class "Default")
      (node (ref "U7") (pin "27") (pinfunction "IO16_27") (pintype "unspecified"))
    )
    (net (code "67") (name "unconnected-(U7-IO17-Pad28)") (class "Default")
      (node (ref "U7") (pin "28") (pinfunction "IO17_28") (pintype "unspecified"))
    )
    (net (code "68") (name "unconnected-(U7-IO35-Pad7)") (class "Default")
      (node (ref "U7") (pin "7") (pinfunction "IO35_7") (pintype "unspecified"))
    )
    (net (code "69") (name "unconnected-(U7-NC-Pad32)") (class "Default")
      (node (ref "U7") (pin "32") (pinfunction "NC_32") (pintype "unspecified"))
    )
    (net (code "70") (name "unconnected-(U7-SD0-Pad21)") (class "Default")
      (node (ref "U7") (pin "21") (pinfunction "SD0_21") (pintype "unspecified"))
    )
    (net (code "71") (name "unconnected-(U7-SD1-Pad22)") (class "Default")
      (node (ref "U7") (pin "22") (pinfunction "SD1_22") (pintype "unspecified"))
    )
    (net (code "72") (name "unconnected-(U7-SD2-Pad17)") (class "Default")
      (node (ref "U7") (pin "17") (pinfunction "SD2_17") (pintype "unspecified"))
    )
    (net (code "73") (name "unconnected-(U7-SD3-Pad18)") (class "Default")
      (node (ref "U7") (pin "18") (pinfunction "SD3_18") (pintype "unspecified"))
    )
    (net (code "74") (name "unconnected-(U7-SENSOR_VN-Pad5)") (class "Default")
      (node (ref "U7") (pin "5") (pinfunction "SENSOR_VN_5") (pintype "unspecified"))
    )
    (net (code "75") (name "unconnected-(U7-SENSOR_VP-Pad4)") (class "Default")
      (node (ref "U7") (pin "4") (pinfunction "SENSOR_VP_4") (pintype "unspecified"))
    )
    (net (code "76") (name "unconnected-(U8-CTS#-Pad9)") (class "Default")
      (node (ref "U8") (pin "9") (pinfunction "CTS#_9") (pintype "unspecified"))
    )
    (net (code "77") (name "unconnected-(U8-DCD#-Pad12)") (class "Default")
      (node (ref "U8") (pin "12") (pinfunction "DCD#_12") (pintype "unspecified"))
    )
    (net (code "78") (name "unconnected-(U8-DSR#-Pad10)") (class "Default")
      (node (ref "U8") (pin "10") (pinfunction "DSR#_10") (pintype "unspecified"))
    )
    (net (code "79") (name "unconnected-(U8-NC.-Pad7)") (class "Default")
      (node (ref "U8") (pin "7") (pinfunction "NC._7") (pintype "unspecified"))
    )
    (net (code "80") (name "unconnected-(U8-NC.-Pad8)") (class "Default")
      (node (ref "U8") (pin "8") (pinfunction "NC._8") (pintype "unspecified"))
    )
    (net (code "81") (name "unconnected-(U8-R232-Pad15)") (class "Default")
      (node (ref "U8") (pin "15") (pinfunction "R232_15") (pintype "unspecified"))
    )
    (net (code "82") (name "unconnected-(U8-RI#-Pad11)") (class "Default")
      (node (ref "U8") (pin "11") (pinfunction "RI#_11") (pintype "unspecified"))
    )
    (net (code "83") (name "unconnected-(U9-CD-Pad9)") (class "Default")
      (node (ref "U9") (pin "9") (pinfunction "CD_9") (pintype "input"))
    )
    (net (code "84") (name "unconnected-(U9-DAT1(RSV)-Pad8)") (class "Default")
      (node (ref "U9") (pin "8") (pinfunction "DAT1(RSV)_8") (pintype "bidirectional"))
    )
    (net (code "85") (name "unconnected-(U9-DAT2(RSV)-Pad1)") (class "Default")
      (node (ref "U9") (pin "1") (pinfunction "DAT2(RSV)_1") (pintype "bidirectional"))
    )
    (net (code "86") (name "unconnected-(U10-AUX_CL-Pad7)") (class "Default")
      (node (ref "U10") (pin "7") (pinfunction "AUX_CL_7") (pintype "unspecified"))
    )
    (net (code "87") (name "unconnected-(U10-AUX_DA-Pad6)") (class "Default")
      (node (ref "U10") (pin "6") (pinfunction "AUX_DA_6") (pintype "unspecified"))
    )
    (net (code "88") (name "unconnected-(U10-INT-Pad12)") (class "Default")
      (node (ref "U10") (pin "12") (pinfunction "INT_12") (pintype "unspecified"))
    )
    (net (code "89") (name "unconnected-(U10-NC-Pad2)") (class "Default")
      (node (ref "U10") (pin "2") (pinfunction "NC_2") (pintype "unspecified"))
    )
    (net (code "90") (name "unconnected-(U10-NC-Pad3)") (class "Default")
      (node (ref "U10") (pin "3") (pinfunction "NC_3") (pintype "unspecified"))
    )
    (net (code "91") (name "unconnected-(U10-NC-Pad4)") (class "Default")
      (node (ref "U10") (pin "4") (pinfunction "NC_4") (pintype "unspecified"))
    )
    (net (code "92") (name "unconnected-(U10-NC-Pad5)") (class "Default")
      (node (ref "U10") (pin "5") (pinfunction "NC_5") (pintype "unspecified"))
    )
    (net (code "93") (name "unconnected-(U10-NC-Pad14)") (class "Default")
      (node (ref "U10") (pin "14") (pinfunction "NC_14") (pintype "unspecified"))
    )
    (net (code "94") (name "unconnected-(U10-NC-Pad15)") (class "Default")
      (node (ref "U10") (pin "15") (pinfunction "NC_15") (pintype "unspecified"))
    )
    (net (code "95") (name "unconnected-(U10-NC-Pad16)") (class "Default")
      (node (ref "U10") (pin "16") (pinfunction "NC_16") (pintype "unspecified"))
    )
    (net (code "96") (name "unconnected-(U10-NC-Pad17)") (class "Default")
      (node (ref "U10") (pin "17") (pinfunction "NC_17") (pintype "unspecified"))
    )
    (net (code "97") (name "unconnected-(U10-RESV-Pad19)") (class "Default")
      (node (ref "U10") (pin "19") (pinfunction "RESV_19") (pintype "unspecified"))
    )
    (net (code "98") (name "unconnected-(U10-RESV-Pad21)") (class "Default")
      (node (ref "U10") (pin "21") (pinfunction "RESV_21") (pintype "unspecified"))
    )
    (net (code "99") (name "unconnected-(U10-RESV-Pad22)") (class "Default")
      (node (ref "U10") (pin "22") (pinfunction "RESV_22") (pintype "unspecified"))
    )
    (net (code "100") (name "unconnected-(U11-DRDY-Pad15)") (class "Default")
      (node (ref "U11") (pin "15") (pinfunction "DRDY_15") (pintype "unspecified"))
    )
    (net (code "101") (name "unconnected-(U11-NC-Pad3)") (class "Default")
      (node (ref "U11") (pin "3") (pinfunction "NC_3") (pintype "unspecified"))
    )
    (net (code "102") (name "unconnected-(U11-NC-Pad5)") (class "Default")
      (node (ref "U11") (pin "5") (pinfunction "NC_5") (pintype "unspecified"))
    )
    (net (code "103") (name "unconnected-(U11-NC-Pad6)") (class "Default")
      (node (ref "U11") (pin "6") (pinfunction "NC_6") (pintype "unspecified"))
    )
    (net (code "104") (name "unconnected-(U11-NC-Pad7)") (class "Default")
      (node (ref "U11") (pin "7") (pinfunction "NC_7") (pintype "unspecified"))
    )
    (net (code "105") (name "unconnected-(U11-NC-Pad14)") (class "Default")
      (node (ref "U11") (pin "14") (pinfunction "NC_14") (pintype "unspecified"))
    )
    (net (code "106") (name "unconnected-(U13-CSB-Pad1)") (class "Default")
      (node (ref "U13") (pin "1") (pinfunction "CSB_1") (pintype "unspecified"))
    )
    (net (code "107") (name "unconnected-(U13-SDO-Pad4)") (class "Default")
      (node (ref "U13") (pin "4") (pinfunction "SDO_4") (pintype "unspecified"))
    )
    (net (code "108") (name "unconnected-(USB1-EH-Pad6)") (class "Default")
      (node (ref "USB1") (pin "6") (pinfunction "EH_6") (pintype "input"))
    )
    (net (code "109") (name "unconnected-(USB1-ID-Pad4)") (class "Default")
      (node (ref "USB1") (pin "4") (pinfunction "ID_4") (pintype "input"))
    )
  )
)
